# Mirror_TurnSignal_-_Connectors_and_Power.net
KiCad netlist of a schematic drawn in Altium Designer
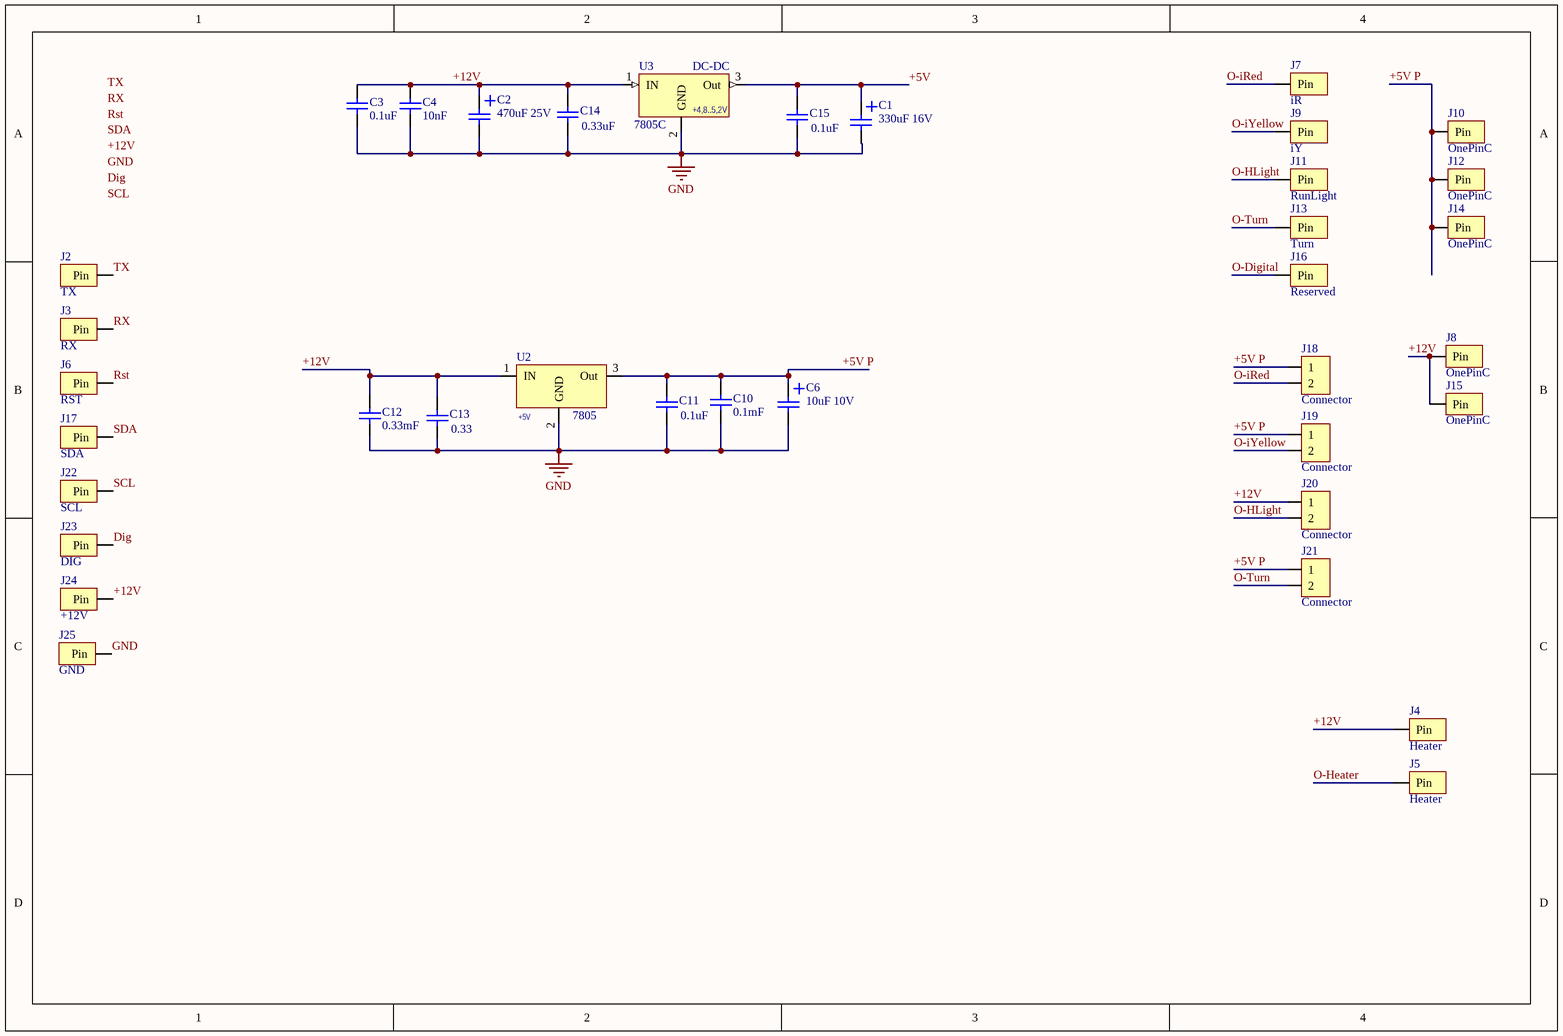
[diagram p0: Mirror TurnSignal - Connectors and Power supply.SchDoc]

(export (version "E")
  (design (tool "Eeschema 10.0.6"))
  (components
    (comp (ref "C1")
      (value "330uF 16V")
      (footprint "Capacitor:Cap E p3.5mm D8xH12 R - PR")
      (description "Capacitor")
      (libsource (lib "Capacitor") (part "Cap Elecrolitic"))
    )
    (comp (ref "C2")
      (value "470uF 25V")
      (footprint "Capacitor:Cap E p2.54mm D4xH8 (2p)")
      (description "Capacitor")
      (libsource (lib "Capacitor") (part "Cap Elecrolitic"))
    )
    (comp (ref "C3")
      (value "0.1uF")
      (footprint "Capacitor:SMD 0805 (2012)")
      (description "Capacitor")
      (libsource (lib "Capacitor") (part "Cap SMD 0402-1812"))
    )
    (comp (ref "C4")
      (value "10nF")
      (footprint "Capacitor:SMD 0805 (2012)")
      (description "Capacitor")
      (libsource (lib "Capacitor") (part "Cap SMD 0402-1812"))
    )
    (comp (ref "C6")
      (value "10uF 10V")
      (footprint "Capacitor:Cap E p1.5mm D4xH8 (2p)")
      (description "Capacitor")
      (libsource (lib "Capacitor") (part "Cap Elecrolitic"))
    )
    (comp (ref "C10")
      (value "0.1mF")
      (footprint "Capacitor:Cap p2.54mm (2p)")
      (description "Capacitor")
      (libsource (lib "Capacitor") (part "Cap Ceramic"))
    )
    (comp (ref "C11")
      (value "0.1uF")
      (footprint "Capacitor:SMD 1206 (3216)")
      (description "Capacitor")
      (libsource (lib "Capacitor") (part "Cap SMD 0402-1812"))
    )
    (comp (ref "C12")
      (value "0.33mF")
      (footprint "Capacitor:Cap p2.54mm (2p)")
      (description "Capacitor")
      (libsource (lib "Capacitor") (part "Cap Ceramic"))
    )
    (comp (ref "C13")
      (value "0.33")
      (footprint "Capacitor:SMD 1206 (3216)")
      (description "Capacitor")
      (libsource (lib "Capacitor") (part "Cap SMD 0402-1812"))
    )
    (comp (ref "C14")
      (value "0.33uF")
      (footprint "Capacitor:SMD 1206 (3216)")
      (description "Capacitor")
      (libsource (lib "Capacitor") (part "Cap SMD 0402-1812"))
    )
    (comp (ref "C15")
      (value "0.1uF")
      (footprint "Capacitor:SMD 1206 (3216)")
      (description "Capacitor")
      (libsource (lib "Capacitor") (part "Cap SMD 0402-1812"))
    )
    (comp (ref "J2")
      (value "TX")
      (footprint "Connector:OnePin 0.7x2")
      (description "Only pad")
      (libsource (lib "Connector") (part "OnePin Connector"))
    )
    (comp (ref "J3")
      (value "RX")
      (footprint "Connector:OnePin 0.7x2")
      (description "Only pad")
      (libsource (lib "Connector") (part "OnePin Connector"))
    )
    (comp (ref "J4")
      (value "Heater")
      (footprint "Connector:OnePin 3x10mm Hole 0.7x8")
      (description "Only pad")
      (libsource (lib "") (part "OnePin Connector_1"))
    )
    (comp (ref "J5")
      (value "Heater")
      (footprint "Connector:OnePin 3x10mm Hole 0.7x8")
      (description "Only pad")
      (libsource (lib "") (part "OnePin Connector_1"))
    )
    (comp (ref "J6")
      (value "RST")
      (footprint "Connector:OnePin 0.7x2")
      (description "Only pad")
      (libsource (lib "Connector") (part "OnePin Connector"))
    )
    (comp (ref "J7")
      (value "iR")
      (footprint "Connector:OnePin 1.2x3")
      (description "Only pad")
      (libsource (lib "") (part "OnePin Connector_1"))
    )
    (comp (ref "J8")
      (value "OnePinC")
      (footprint "Connector:OnePin 1.2x3")
      (description "Only pad")
      (libsource (lib "") (part "OnePin Connector_1"))
    )
    (comp (ref "J9")
      (value "iY")
      (footprint "Connector:OnePin 1.2x3")
      (description "Only pad")
      (libsource (lib "") (part "OnePin Connector_1"))
    )
    (comp (ref "J10")
      (value "OnePinC")
      (footprint "Connector:OnePin 1.2x3")
      (description "Only pad")
      (libsource (lib "") (part "OnePin Connector_1"))
    )
    (comp (ref "J11")
      (value "RunLight")
      (footprint "Connector:OnePin 1.2x3")
      (description "Only pad")
      (libsource (lib "") (part "OnePin Connector_1"))
    )
    (comp (ref "J12")
      (value "OnePinC")
      (footprint "Connector:OnePin 1.2x3")
      (description "Only pad")
      (libsource (lib "") (part "OnePin Connector_1"))
    )
    (comp (ref "J13")
      (value "Turn")
      (footprint "Connector:OnePin 1.2x3")
      (description "Only pad")
      (libsource (lib "") (part "OnePin Connector_1"))
    )
    (comp (ref "J14")
      (value "OnePinC")
      (footprint "Connector:OnePin 1.2x3")
      (description "Only pad")
      (libsource (lib "") (part "OnePin Connector_1"))
    )
    (comp (ref "J15")
      (value "OnePinC")
      (footprint "Connector:OnePin 1.2x3")
      (description "Only pad")
      (libsource (lib "") (part "OnePin Connector_1"))
    )
    (comp (ref "J16")
      (value "Reserved")
      (footprint "Connector:OnePin 1.2x3")
      (description "Only pad")
      (libsource (lib "") (part "OnePin Connector_1"))
    )
    (comp (ref "J17")
      (value "SDA")
      (footprint "Connector:OnePin 0.7x2")
      (description "Only pad")
      (libsource (lib "Connector") (part "OnePin Connector"))
    )
    (comp (ref "J18")
      (value "Connector")
      (footprint "Connector:CWF-2")
      (description "CWF series")
      (libsource (lib "Connector") (part "CWF-2 (R)"))
    )
    (comp (ref "J19")
      (value "Connector")
      (footprint "Connector:CWF-2")
      (description "CWF series")
      (libsource (lib "Connector") (part "CWF-2 (R)"))
    )
    (comp (ref "J20")
      (value "Connector")
      (footprint "Connector:CWF-2")
      (description "CWF series")
      (libsource (lib "Connector") (part "CWF-2 (R)"))
    )
    (comp (ref "J21")
      (value "Connector")
      (footprint "Connector:CWF-2")
      (description "CWF series")
      (libsource (lib "Connector") (part "CWF-2 (R)"))
    )
    (comp (ref "J22")
      (value "SCL")
      (footprint "Connector:OnePin 0.7x2")
      (description "Only pad")
      (libsource (lib "Connector") (part "OnePin Connector"))
    )
    (comp (ref "J23")
      (value "DIG")
      (footprint "Connector:OnePin 0.7x2")
      (description "Only pad")
      (libsource (lib "Connector") (part "OnePin Connector"))
    )
    (comp (ref "J24")
      (value "+12V")
      (footprint "Connector:OnePin 0.7x2")
      (description "Only pad")
      (libsource (lib "Connector") (part "OnePin Connector"))
    )
    (comp (ref "J25")
      (value "GND")
      (footprint "Connector:OnePin 0.7x2")
      (description "Only pad")
      (libsource (lib "Connector") (part "OnePin Connector"))
    )
    (comp (ref "U2")
      (value "7805")
      (footprint "GeneralCases:TO220 L")
      (description "Linear Voltage Regulator")
      (fields (field (name "V OUT") "+5V"))
      (libsource (lib "PowerAdjusment") (part "KPEH"))
    )
    (comp (ref "U3")
      (value "7805C")
      (footprint "GeneralCases:D-PAK")
      (description "Voltage Regulator")
      (fields (field (name "MANUFACTURER") "Интеграл") (field (name "V OUT") "+4,8..5,2V"))
      (libsource (lib "PowerAdjusment") (part "7805C"))
    )
  )
  (nets
    (net (code "1") (name "/+5V") (class "Default")
      (node (ref "C1") (pin "1") (pinfunction "1_1") (pintype "passive"))
      (node (ref "C15") (pin "1") (pinfunction "1_1") (pintype "passive"))
      (node (ref "U3") (pin "3") (pinfunction "Out_3") (pintype "output"))
    )
    (net (code "2") (name "/+5V P") (class "Default")
      (node (ref "C10") (pin "1") (pinfunction "1_1") (pintype "passive"))
      (node (ref "C11") (pin "1") (pinfunction "1_1") (pintype "passive"))
      (node (ref "C6") (pin "1") (pinfunction "1_1") (pintype "passive"))
      (node (ref "J10") (pin "1") (pinfunction "Pin_1") (pintype "passive"))
      (node (ref "J12") (pin "1") (pinfunction "Pin_1") (pintype "passive"))
      (node (ref "J14") (pin "1") (pinfunction "Pin_1") (pintype "passive"))
      (node (ref "J18") (pin "1") (pinfunction "1_1") (pintype "passive"))
      (node (ref "J19") (pin "1") (pinfunction "1_1") (pintype "passive"))
      (node (ref "J21") (pin "1") (pinfunction "1_1") (pintype "passive"))
      (node (ref "U2") (pin "3") (pinfunction "Out_3") (pintype "power_in"))
    )
    (net (code "3") (name "/+12V") (class "Default")
      (node (ref "C12") (pin "1") (pinfunction "1_1") (pintype "passive"))
      (node (ref "C13") (pin "1") (pinfunction "1_1") (pintype "passive"))
      (node (ref "C14") (pin "1") (pinfunction "1_1") (pintype "passive"))
      (node (ref "C2") (pin "1") (pinfunction "1_1") (pintype "passive"))
      (node (ref "C3") (pin "1") (pinfunction "1_1") (pintype "passive"))
      (node (ref "C4") (pin "1") (pinfunction "1_1") (pintype "passive"))
      (node (ref "J15") (pin "1") (pinfunction "Pin_1") (pintype "passive"))
      (node (ref "J20") (pin "1") (pinfunction "1_1") (pintype "passive"))
      (node (ref "J24") (pin "1") (pinfunction "Pin_1") (pintype "passive"))
      (node (ref "J4") (pin "1") (pinfunction "Pin_1") (pintype "passive"))
      (node (ref "J8") (pin "1") (pinfunction "Pin_1") (pintype "passive"))
      (node (ref "U2") (pin "1") (pinfunction "IN_1") (pintype "power_in"))
      (node (ref "U3") (pin "1") (pinfunction "IN_1") (pintype "input"))
    )
    (net (code "4") (name "/Dig") (class "Default")
      (node (ref "J23") (pin "1") (pinfunction "Pin_1") (pintype "passive"))
    )
    (net (code "5") (name "/O-Digital") (class "Default")
      (node (ref "J16") (pin "1") (pinfunction "Pin_1") (pintype "passive"))
    )
    (net (code "6") (name "/O-HLight") (class "Default")
      (node (ref "J11") (pin "1") (pinfunction "Pin_1") (pintype "passive"))
      (node (ref "J20") (pin "2") (pinfunction "2_2") (pintype "passive"))
    )
    (net (code "7") (name "/O-Heater") (class "Default")
      (node (ref "J5") (pin "1") (pinfunction "Pin_1") (pintype "passive"))
    )
    (net (code "8") (name "/O-Turn") (class "Default")
      (node (ref "J13") (pin "1") (pinfunction "Pin_1") (pintype "passive"))
      (node (ref "J21") (pin "2") (pinfunction "2_2") (pintype "passive"))
    )
    (net (code "9") (name "/O-iRed") (class "Default")
      (node (ref "J18") (pin "2") (pinfunction "2_2") (pintype "passive"))
      (node (ref "J7") (pin "1") (pinfunction "Pin_1") (pintype "passive"))
    )
    (net (code "10") (name "/O-iYellow") (class "Default")
      (node (ref "J19") (pin "2") (pinfunction "2_2") (pintype "passive"))
      (node (ref "J9") (pin "1") (pinfunction "Pin_1") (pintype "passive"))
    )
    (net (code "11") (name "/RX") (class "Default")
      (node (ref "J3") (pin "1") (pinfunction "Pin_1") (pintype "passive"))
    )
    (net (code "12") (name "/Rst") (class "Default")
      (node (ref "J6") (pin "1") (pinfunction "Pin_1") (pintype "passive"))
    )
    (net (code "13") (name "/SCL") (class "Default")
      (node (ref "J22") (pin "1") (pinfunction "Pin_1") (pintype "passive"))
    )
    (net (code "14") (name "/SDA") (class "Default")
      (node (ref "J17") (pin "1") (pinfunction "Pin_1") (pintype "passive"))
    )
    (net (code "15") (name "/TX") (class "Default")
      (node (ref "J2") (pin "1") (pinfunction "Pin_1") (pintype "passive"))
    )
    (net (code "16") (name "GND") (class "Default")
      (node (ref "C1") (pin "2") (pinfunction "2_2") (pintype "passive"))
      (node (ref "C10") (pin "2") (pinfunction "2_2") (pintype "passive"))
      (node (ref "C11") (pin "2") (pinfunction "2_2") (pintype "passive"))
      (node (ref "C12") (pin "2") (pinfunction "2_2") (pintype "passive"))
      (node (ref "C13") (pin "2") (pinfunction "2_2") (pintype "passive"))
      (node (ref "C14") (pin "2") (pinfunction "2_2") (pintype "passive"))
      (node (ref "C15") (pin "2") (pinfunction "2_2") (pintype "passive"))
      (node (ref "C2") (pin "2") (pinfunction "2_2") (pintype "passive"))
      (node (ref "C3") (pin "2") (pinfunction "2_2") (pintype "passive"))
      (node (ref "C4") (pin "2") (pinfunction "2_2") (pintype "passive"))
      (node (ref "C6") (pin "2") (pinfunction "2_2") (pintype "passive"))
      (node (ref "J25") (pin "1") (pinfunction "Pin_1") (pintype "passive"))
      (node (ref "U2") (pin "2") (pinfunction "GND_2") (pintype "passive"))
      (node (ref "U3") (pin "2") (pinfunction "GND_2") (pintype "passive"))
    )
  )
)
